# truth.net
KiCad netlist of a schematic drawn in EAGLE
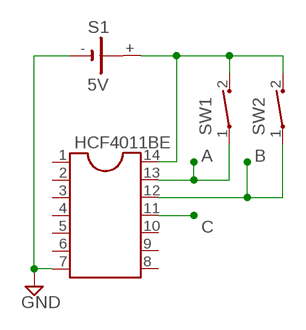
[diagram p0: schematic, sheet 1]

(export (version "E")
  (design (tool "Eeschema 10.0.6"))
  (components
    (comp (ref "HCF4011BE")
      (value "DIL14")
      (footprint "eagle-import:DIL14")
      (libsource (lib "eagle-import") (part "DIL14"))
    )
    (comp (ref "S1")
      (value "5V")
      (footprint "eagle-import:CRAA")
      (libsource (lib "eagle-import") (part "CRAA"))
    )
    (comp (ref "SW1")
      (value "CT10-XXXX-G4")
      (footprint "eagle-import:CT10-XXXX-G4")
      (libsource (lib "eagle-import") (part "CT10-XXXX-G4"))
    )
    (comp (ref "SW2")
      (value "CT10-XXXX-G4")
      (footprint "eagle-import:CT10-XXXX-G4")
      (libsource (lib "eagle-import") (part "CT10-XXXX-G4"))
    )
  )
  (nets
    (net (code "1") (name "GND") (class "Default")
      (node (ref "HCF4011BE") (pin "7") (pinfunction "7_7") (pintype "passive"))
      (node (ref "S1") (pin "-") (pinfunction "-_-") (pintype "passive"))
    )
    (net (code "2") (name "Net-(HCF4011BE-Pad12)") (class "Default")
      (node (ref "HCF4011BE") (pin "12") (pinfunction "12_12") (pintype "passive"))
      (node (ref "SW2") (pin "1") (pinfunction "1_1") (pintype "passive"))
    )
    (net (code "3") (name "Net-(HCF4011BE-Pad13)") (class "Default")
      (node (ref "HCF4011BE") (pin "13") (pinfunction "13_13") (pintype "passive"))
      (node (ref "SW1") (pin "1") (pinfunction "1_1") (pintype "passive"))
    )
    (net (code "4") (name "Net-(HCF4011BE-Pad14)") (class "Default")
      (node (ref "HCF4011BE") (pin "14") (pinfunction "14_14") (pintype "passive"))
      (node (ref "S1") (pin "+") (pinfunction "+_+") (pintype "passive"))
      (node (ref "SW1") (pin "2") (pinfunction "2_2") (pintype "passive"))
      (node (ref "SW2") (pin "2") (pinfunction "2_2") (pintype "passive"))
    )
    (net (code "5") (name "unconnected-(HCF4011BE-Pad1)") (class "Default")
      (node (ref "HCF4011BE") (pin "1") (pinfunction "1_1") (pintype "passive"))
    )
    (net (code "6") (name "unconnected-(HCF4011BE-Pad2)") (class "Default")
      (node (ref "HCF4011BE") (pin "2") (pinfunction "2_2") (pintype "passive"))
    )
    (net (code "7") (name "unconnected-(HCF4011BE-Pad3)") (class "Default")
      (node (ref "HCF4011BE") (pin "3") (pinfunction "3_3") (pintype "passive"))
    )
    (net (code "8") (name "unconnected-(HCF4011BE-Pad4)") (class "Default")
      (node (ref "HCF4011BE") (pin "4") (pinfunction "4_4") (pintype "passive"))
    )
    (net (code "9") (name "unconnected-(HCF4011BE-Pad5)") (class "Default")
      (node (ref "HCF4011BE") (pin "5") (pinfunction "5_5") (pintype "passive"))
    )
    (net (code "10") (name "unconnected-(HCF4011BE-Pad6)") (class "Default")
      (node (ref "HCF4011BE") (pin "6") (pinfunction "6_6") (pintype "passive"))
    )
    (net (code "11") (name "unconnected-(HCF4011BE-Pad8)") (class "Default")
      (node (ref "HCF4011BE") (pin "8") (pinfunction "8_8") (pintype "passive"))
    )
    (net (code "12") (name "unconnected-(HCF4011BE-Pad9)") (class "Default")
      (node (ref "HCF4011BE") (pin "9") (pinfunction "9_9") (pintype "passive"))
    )
    (net (code "13") (name "unconnected-(HCF4011BE-Pad10)") (class "Default")
      (node (ref "HCF4011BE") (pin "10") (pinfunction "10_10") (pintype "passive"))
    )
    (net (code "14") (name "unconnected-(HCF4011BE-Pad11)") (class "Default")
      (node (ref "HCF4011BE") (pin "11") (pinfunction "11_11") (pintype "passive"))
    )
    (net (code "15") (name "unconnected-(S1-+-Pad+@1)") (class "Default")
      (node (ref "S1") (pin "+@1") (pinfunction "+_+@1") (pintype "passive"))
    )
  )
)
